# schematIMIKU.net
KiCad netlist of a schematic drawn in EAGLE
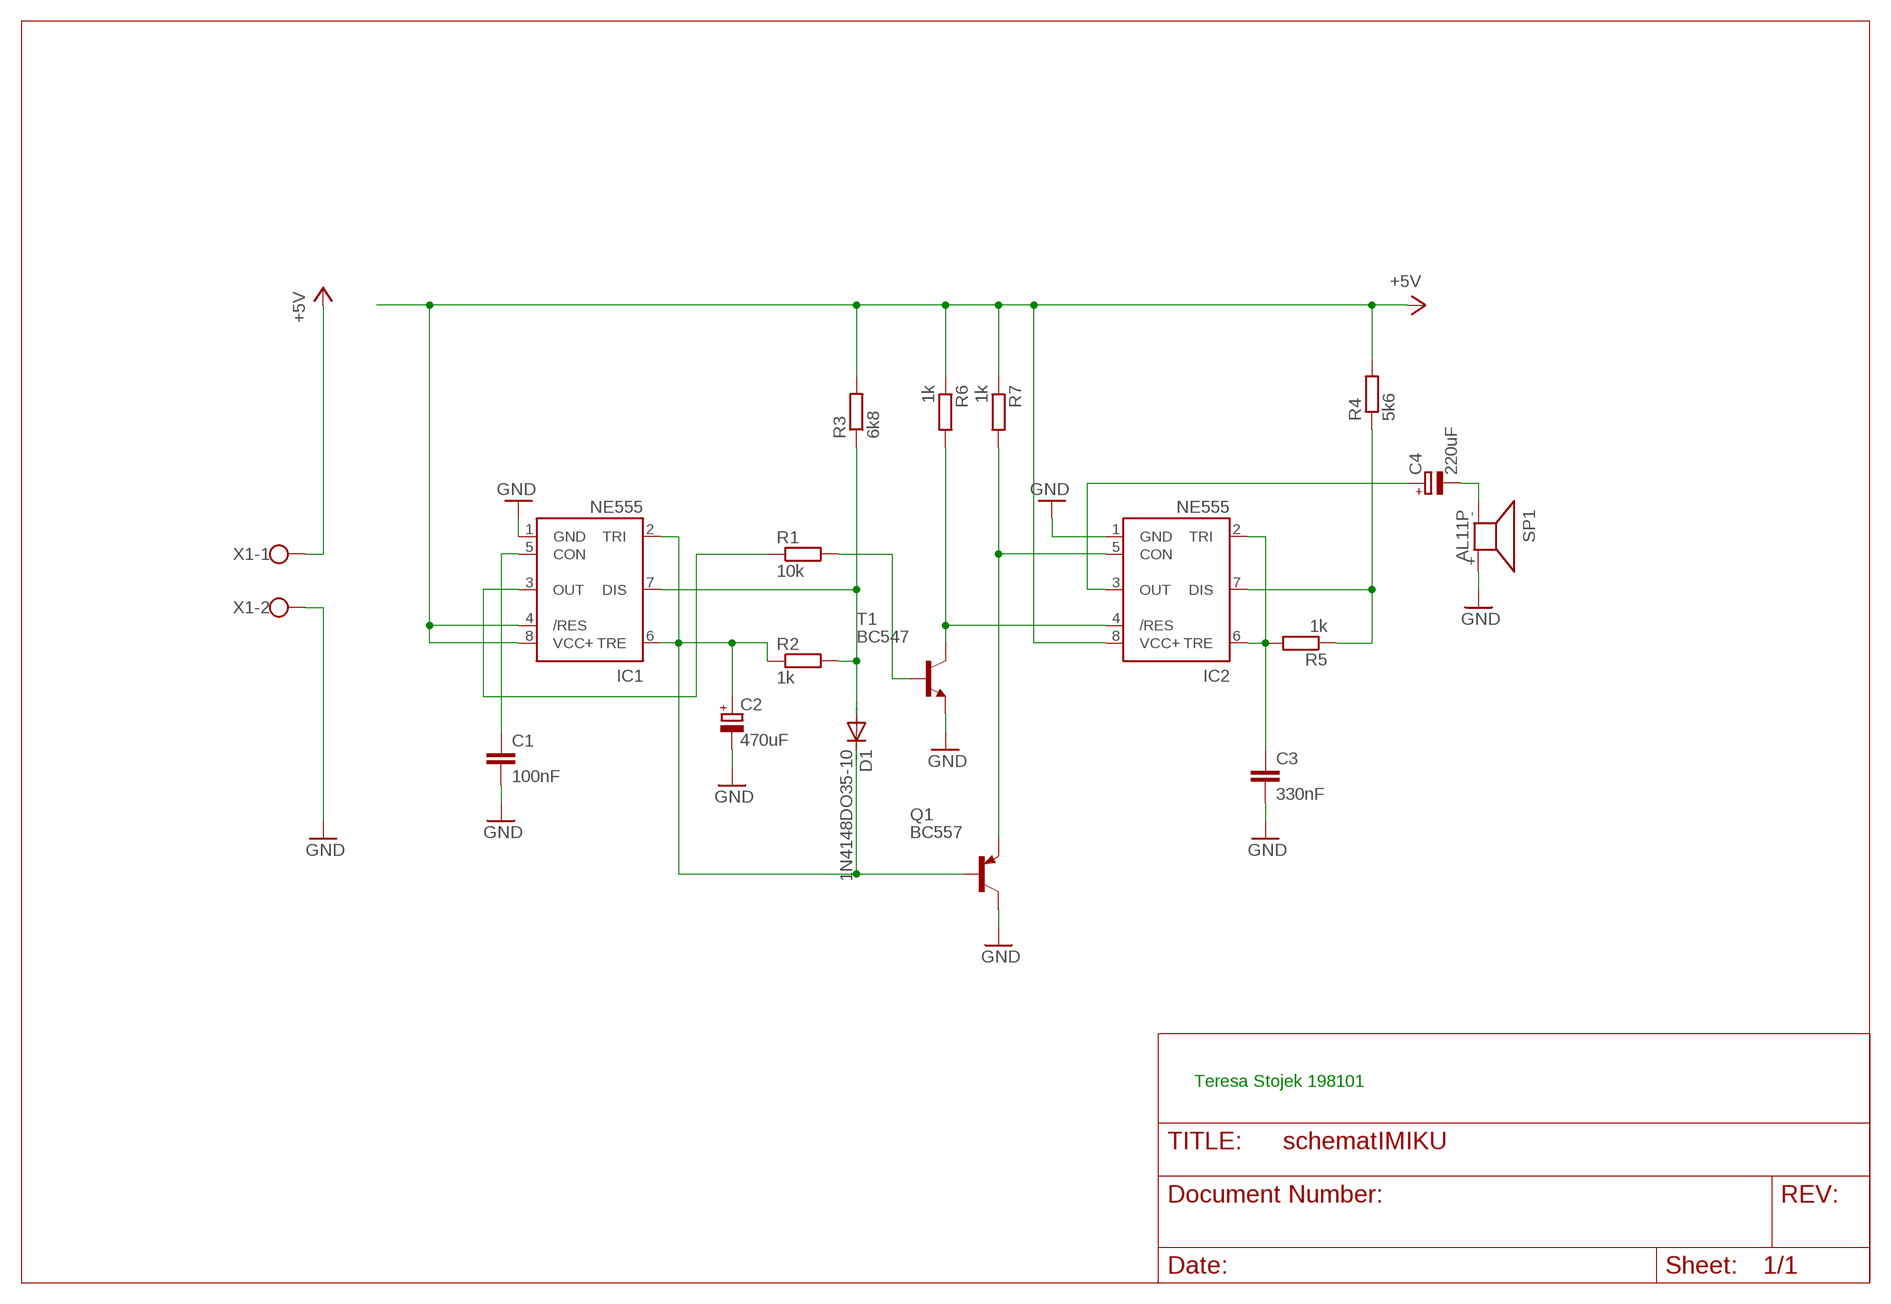
[diagram p0: schematic, sheet 1]

(export (version "E")
  (design (tool "Eeschema 10.0.6"))
  (components
    (comp (ref "C1")
      (value "100nF")
      (footprint "eagle-import:C050-050X075")
      (libsource (lib "eagle-import") (part "C-EU050-050X075"))
    )
    (comp (ref "C2")
      (value "470uF")
      (footprint "eagle-import:140CLH-1014")
      (libsource (lib "eagle-import") (part "CPOL-EU140CLH-1014"))
    )
    (comp (ref "C3")
      (value "330nF")
      (footprint "eagle-import:C050-050X075")
      (libsource (lib "eagle-import") (part "C-EU050-050X075"))
    )
    (comp (ref "C4")
      (value "220uF")
      (footprint "eagle-import:140CLH-1014")
      (libsource (lib "eagle-import") (part "CPOL-EU140CLH-1014"))
    )
    (comp (ref "D1")
      (value "1N4148DO35-10")
      (footprint "eagle-import:DO35-10")
      (libsource (lib "eagle-import") (part "1N4148DO35-10"))
    )
    (comp (ref "IC1")
      (value "NE555")
      (footprint "eagle-import:DIL-08")
      (fields (field (name "MF") "Arrow Electronics") (field (name "MPN") "NE555N"))
      (libsource (lib "eagle-import") (part "NE555"))
    )
    (comp (ref "IC2")
      (value "NE555")
      (footprint "eagle-import:DIL-08")
      (fields (field (name "MF") "Arrow Electronics") (field (name "MPN") "NE555N"))
      (libsource (lib "eagle-import") (part "NE555"))
    )
    (comp (ref "Q1")
      (value "BC557")
      (footprint "eagle-import:TO92")
      (libsource (lib "eagle-import") (part "BC557"))
    )
    (comp (ref "R1")
      (value "10k")
      (footprint "eagle-import:0207_10")
      (libsource (lib "eagle-import") (part "R-EU_0207/10"))
    )
    (comp (ref "R2")
      (value "1k")
      (footprint "eagle-import:0207_10")
      (libsource (lib "eagle-import") (part "R-EU_0207/10"))
    )
    (comp (ref "R3")
      (value "6k8")
      (footprint "eagle-import:0207_10")
      (libsource (lib "eagle-import") (part "R-EU_0207/10"))
    )
    (comp (ref "R4")
      (value "5k6")
      (footprint "eagle-import:0207_10")
      (libsource (lib "eagle-import") (part "R-EU_0207/10"))
    )
    (comp (ref "R5")
      (value "1k")
      (footprint "eagle-import:0207_10")
      (libsource (lib "eagle-import") (part "R-EU_0207/10"))
    )
    (comp (ref "R6")
      (value "1k")
      (footprint "eagle-import:0207_10")
      (libsource (lib "eagle-import") (part "R-EU_0207/10"))
    )
    (comp (ref "R7")
      (value "1k")
      (footprint "eagle-import:0207_10")
      (libsource (lib "eagle-import") (part "R-EU_0207/10"))
    )
    (comp (ref "SP1")
      (value "AL11P")
      (footprint "eagle-import:AL11P")
      (libsource (lib "eagle-import") (part "AL11P"))
    )
    (comp (ref "T1")
      (value "BC547")
      (footprint "eagle-import:TO92")
      (libsource (lib "eagle-import") (part "BC547"))
    )
    (comp (ref "X1")
      (value "W237-102")
      (footprint "eagle-import:W237-102")
      (fields (field (name "MPN") "237-102"))
      (libsource (lib "eagle-import") (part "W237-102"))
    )
  )
  (nets
    (net (code "1") (name "+5V") (class "Default")
      (node (ref "IC1") (pin "4") (pinfunction "/RES_4") (pintype "input"))
      (node (ref "IC1") (pin "8") (pinfunction "VCC+_8") (pintype "power_in"))
      (node (ref "IC2") (pin "8") (pinfunction "VCC+_8") (pintype "power_in"))
      (node (ref "R3") (pin "2") (pinfunction "2_2") (pintype "passive"))
      (node (ref "R4") (pin "2") (pinfunction "2_2") (pintype "passive"))
      (node (ref "R6") (pin "1") (pinfunction "1_1") (pintype "passive"))
      (node (ref "R7") (pin "1") (pinfunction "1_1") (pintype "passive"))
      (node (ref "X1") (pin "1") (pinfunction "KL_1") (pintype "passive"))
    )
    (net (code "2") (name "GND") (class "Default")
      (node (ref "C1") (pin "2") (pinfunction "2_2") (pintype "passive"))
      (node (ref "C2") (pin "-") (pinfunction "-_-") (pintype "passive"))
      (node (ref "C3") (pin "2") (pinfunction "2_2") (pintype "passive"))
      (node (ref "IC1") (pin "1") (pinfunction "GND_1") (pintype "power_in"))
      (node (ref "IC2") (pin "1") (pinfunction "GND_1") (pintype "power_in"))
      (node (ref "Q1") (pin "3") (pinfunction "C_3") (pintype "passive"))
      (node (ref "SP1") (pin "+") (pinfunction "2_+") (pintype "passive"))
      (node (ref "T1") (pin "1") (pinfunction "E_1") (pintype "passive"))
      (node (ref "X1") (pin "2") (pinfunction "KL_2") (pintype "passive"))
    )
    (net (code "3") (name "Net-(IC1-CON)") (class "Default")
      (node (ref "C1") (pin "1") (pinfunction "1_1") (pintype "passive"))
      (node (ref "IC1") (pin "5") (pinfunction "CON_5") (pintype "input"))
    )
    (net (code "4") (name "Net-(IC1-DIS)") (class "Default")
      (node (ref "D1") (pin "A") (pinfunction "A_A") (pintype "passive"))
      (node (ref "IC1") (pin "7") (pinfunction "DIS_7") (pintype "input"))
      (node (ref "R2") (pin "2") (pinfunction "2_2") (pintype "passive"))
      (node (ref "R3") (pin "1") (pinfunction "1_1") (pintype "passive"))
    )
    (net (code "5") (name "Net-(IC1-OUT)") (class "Default")
      (node (ref "IC1") (pin "3") (pinfunction "OUT_3") (pintype "output"))
      (node (ref "R1") (pin "1") (pinfunction "1_1") (pintype "passive"))
    )
    (net (code "6") (name "Net-(IC1-TRE)") (class "Default")
      (node (ref "C2") (pin "+") (pinfunction "+_+") (pintype "passive"))
      (node (ref "D1") (pin "C") (pinfunction "C_C") (pintype "passive"))
      (node (ref "IC1") (pin "2") (pinfunction "TRI_2") (pintype "input"))
      (node (ref "IC1") (pin "6") (pinfunction "TRE_6") (pintype "input"))
      (node (ref "Q1") (pin "2") (pinfunction "B_2") (pintype "passive"))
      (node (ref "R2") (pin "1") (pinfunction "1_1") (pintype "passive"))
    )
    (net (code "7") (name "Net-(IC2-CON)") (class "Default")
      (node (ref "IC2") (pin "5") (pinfunction "CON_5") (pintype "input"))
      (node (ref "Q1") (pin "1") (pinfunction "E_1") (pintype "passive"))
      (node (ref "R7") (pin "2") (pinfunction "2_2") (pintype "passive"))
    )
    (net (code "8") (name "Net-(IC2-DIS)") (class "Default")
      (node (ref "IC2") (pin "7") (pinfunction "DIS_7") (pintype "input"))
      (node (ref "R4") (pin "1") (pinfunction "1_1") (pintype "passive"))
      (node (ref "R5") (pin "1") (pinfunction "1_1") (pintype "passive"))
    )
    (net (code "9") (name "Net-(IC2-OUT)") (class "Default")
      (node (ref "C4") (pin "+") (pinfunction "+_+") (pintype "passive"))
      (node (ref "IC2") (pin "3") (pinfunction "OUT_3") (pintype "output"))
    )
    (net (code "10") (name "Net-(IC2-TRE)") (class "Default")
      (node (ref "C3") (pin "1") (pinfunction "1_1") (pintype "passive"))
      (node (ref "IC2") (pin "2") (pinfunction "TRI_2") (pintype "input"))
      (node (ref "IC2") (pin "6") (pinfunction "TRE_6") (pintype "input"))
      (node (ref "R5") (pin "2") (pinfunction "2_2") (pintype "passive"))
    )
    (net (code "11") (name "Net-(IC2-{slash}RES)") (class "Default")
      (node (ref "IC2") (pin "4") (pinfunction "/RES_4") (pintype "input"))
      (node (ref "R6") (pin "2") (pinfunction "2_2") (pintype "passive"))
      (node (ref "T1") (pin "3") (pinfunction "C_3") (pintype "passive"))
    )
    (net (code "12") (name "Net-(SP1-1)") (class "Default")
      (node (ref "C4") (pin "-") (pinfunction "-_-") (pintype "passive"))
      (node (ref "SP1") (pin "-") (pinfunction "1_-") (pintype "passive"))
    )
    (net (code "13") (name "Net-(T1-B)") (class "Default")
      (node (ref "R1") (pin "2") (pinfunction "2_2") (pintype "passive"))
      (node (ref "T1") (pin "2") (pinfunction "B_2") (pintype "passive"))
    )
  )
)
